# TS1.net
KiCad netlist of a schematic drawn in EAGLE
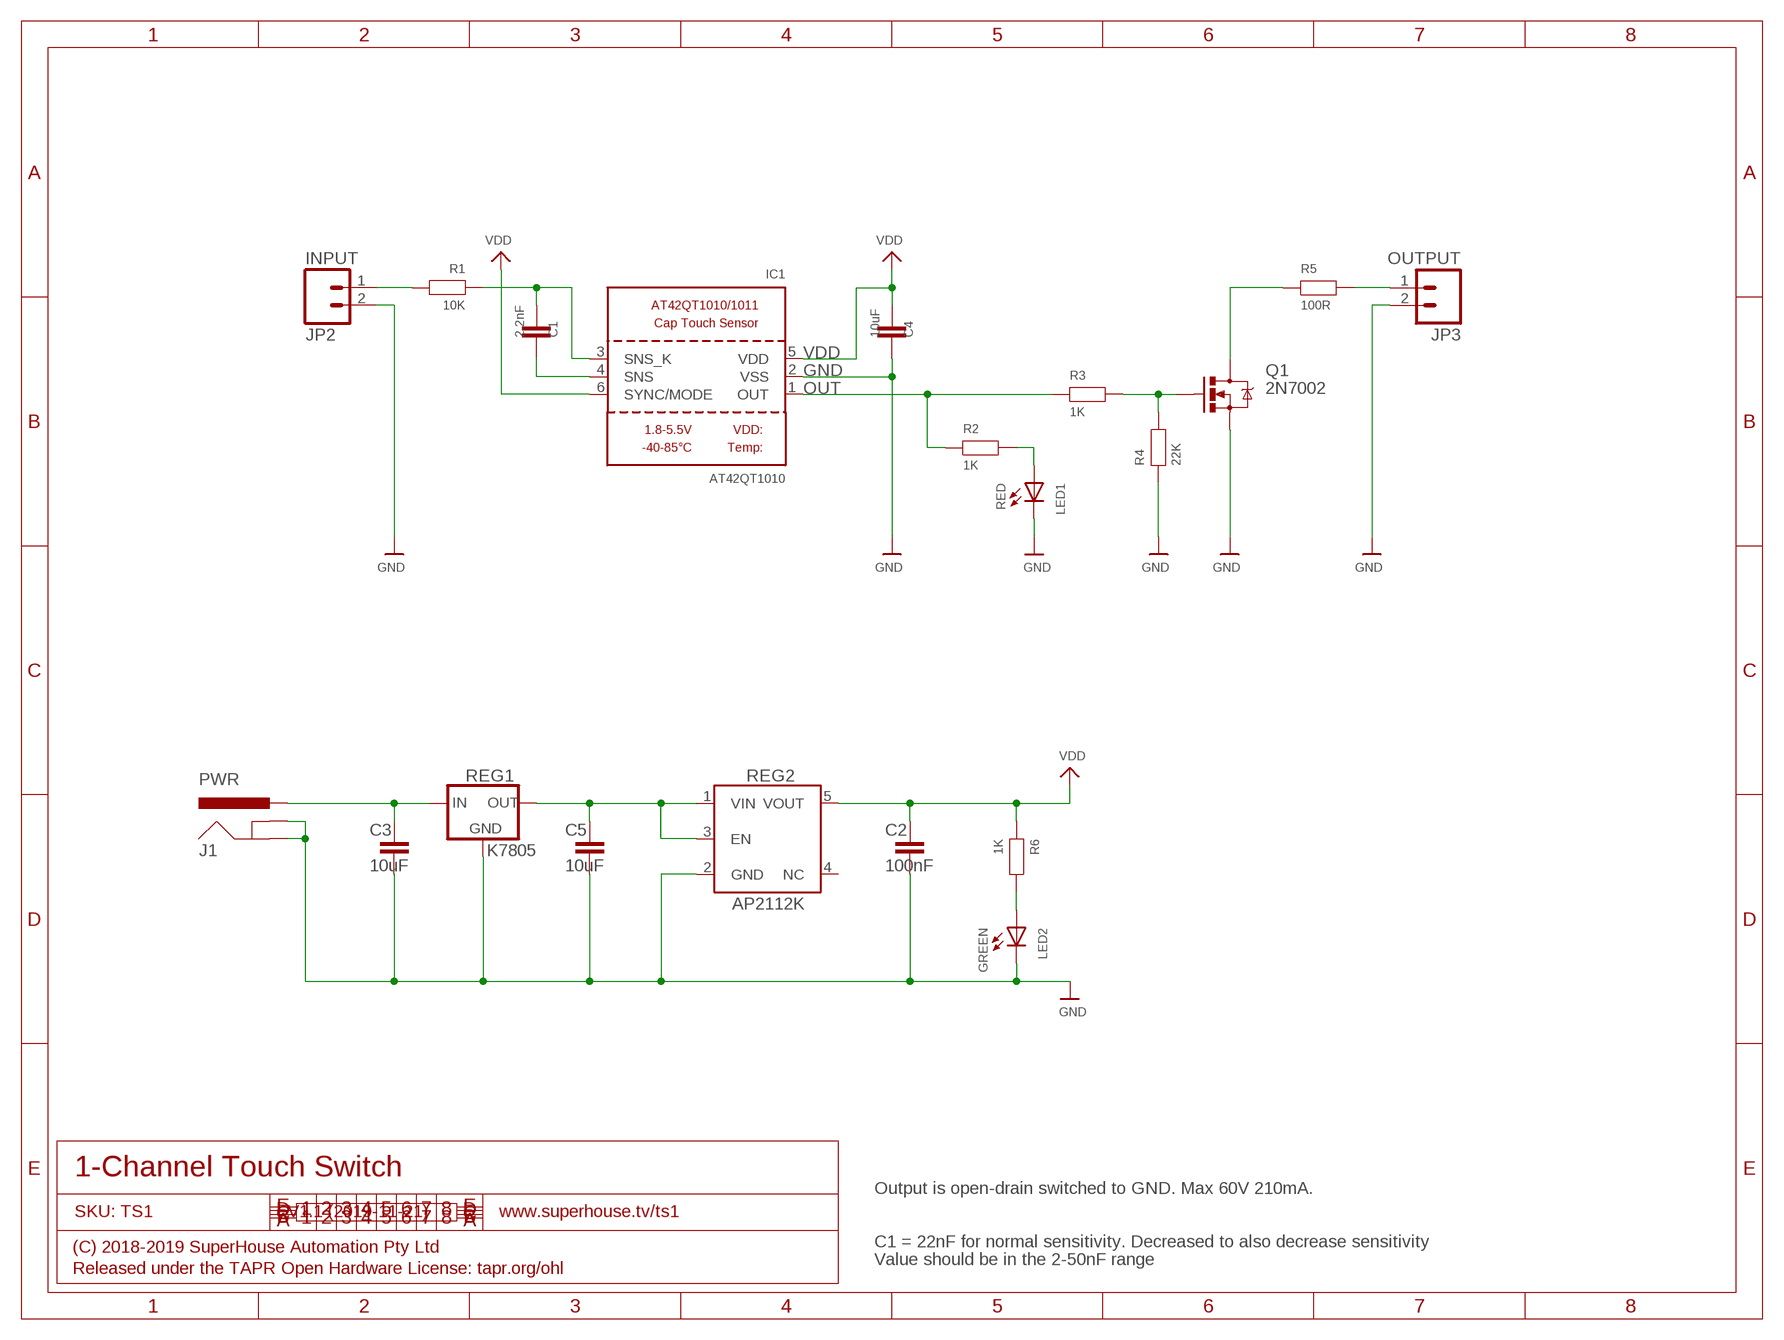
[diagram p0: schematic, sheet 1]

(export (version "E")
  (design (tool "Eeschema 10.0.6"))
  (components
    (comp (ref "C1")
      (value "2.2nF")
      (footprint "eagle-import:C0603")
      (libsource (lib "eagle-import") (part "CAP0603"))
    )
    (comp (ref "C2")
      (value "100nF")
      (footprint "eagle-import:C0603")
      (libsource (lib "eagle-import") (part "CAP0603"))
    )
    (comp (ref "C3")
      (value "10uF")
      (footprint "eagle-import:C0603")
      (libsource (lib "eagle-import") (part "CAP0603"))
    )
    (comp (ref "C4")
      (value "10uF")
      (footprint "eagle-import:C0603")
      (libsource (lib "eagle-import") (part "CAP0603"))
    )
    (comp (ref "C5")
      (value "10uF")
      (footprint "eagle-import:C0603")
      (libsource (lib "eagle-import") (part "CAP0603"))
    )
    (comp (ref "IC1")
      (value "AT42QT1010")
      (footprint "eagle-import:SOT23-6")
      (libsource (lib "eagle-import") (part "AT42QT1010/1"))
    )
    (comp (ref "J1")
      (value "PWR")
      (footprint "eagle-import:POWER_JACK_SLOTS")
      (libsource (lib "eagle-import") (part "POWER_JACK-SLOTS"))
    )
    (comp (ref "JP2")
      (value "INPUT")
      (footprint "eagle-import:1X02-S")
      (libsource (lib "eagle-import") (part "M02-SOCKET"))
    )
    (comp (ref "JP3")
      (value "OUTPUT")
      (footprint "eagle-import:1X02-S")
      (libsource (lib "eagle-import") (part "M02-SOCKET"))
    )
    (comp (ref "LED1")
      (value "RED")
      (footprint "eagle-import:LED-0603")
      (libsource (lib "eagle-import") (part "LED0603"))
    )
    (comp (ref "LED2")
      (value "GREEN")
      (footprint "eagle-import:LED-0603")
      (libsource (lib "eagle-import") (part "LED0603"))
    )
    (comp (ref "Q1")
      (value "2N7002")
      (footprint "eagle-import:SOT23-3")
      (libsource (lib "eagle-import") (part "MOSFET-NCHANNEL-233"))
    )
    (comp (ref "R1")
      (value "10K")
      (footprint "eagle-import:R0603")
      (libsource (lib "eagle-import") (part "RESISTOR0603"))
    )
    (comp (ref "R2")
      (value "1K")
      (footprint "eagle-import:R0603")
      (libsource (lib "eagle-import") (part "RESISTOR0603"))
    )
    (comp (ref "R3")
      (value "1K")
      (footprint "eagle-import:R0603")
      (libsource (lib "eagle-import") (part "RESISTOR0603"))
    )
    (comp (ref "R4")
      (value "22K")
      (footprint "eagle-import:R0603")
      (libsource (lib "eagle-import") (part "RESISTOR0603"))
    )
    (comp (ref "R5")
      (value "100R")
      (footprint "eagle-import:R0603")
      (libsource (lib "eagle-import") (part "RESISTOR0603"))
    )
    (comp (ref "R6")
      (value "1K")
      (footprint "eagle-import:R0603")
      (libsource (lib "eagle-import") (part "RESISTOR0603"))
    )
    (comp (ref "REG1")
      (value "K7805")
      (footprint "eagle-import:K78XX-500R3")
      (libsource (lib "eagle-import") (part "K78XX-500R3"))
    )
    (comp (ref "REG2")
      (value "AP2112KSOT25")
      (footprint "eagle-import:SOT23-5")
      (libsource (lib "eagle-import") (part "AP2112KSOT25"))
    )
  )
  (nets
    (net (code "1") (name "/OUT") (class "Default")
      (node (ref "IC1") (pin "1") (pinfunction "OUT_1") (pintype "output"))
      (node (ref "R2") (pin "1") (pinfunction "1_1") (pintype "passive"))
      (node (ref "R3") (pin "1") (pinfunction "1_1") (pintype "passive"))
    )
    (net (code "2") (name "GND") (class "Default")
      (node (ref "C2") (pin "2") (pinfunction "2_2") (pintype "passive"))
      (node (ref "C3") (pin "2") (pinfunction "2_2") (pintype "passive"))
      (node (ref "C4") (pin "2") (pinfunction "2_2") (pintype "passive"))
      (node (ref "C5") (pin "2") (pinfunction "2_2") (pintype "passive"))
      (node (ref "IC1") (pin "2") (pinfunction "VSS_2") (pintype "power_in"))
      (node (ref "J1") (pin "GND") (pinfunction "GND_GND") (pintype "bidirectional"))
      (node (ref "J1") (pin "GNDBREAK") (pinfunction "GNDBREAK_GNDBREAK") (pintype "bidirectional"))
      (node (ref "JP2") (pin "2") (pinfunction "2_2") (pintype "passive"))
      (node (ref "JP3") (pin "2") (pinfunction "2_2") (pintype "passive"))
      (node (ref "LED1") (pin "C") (pinfunction "C_C") (pintype "passive"))
      (node (ref "LED2") (pin "C") (pinfunction "C_C") (pintype "passive"))
      (node (ref "Q1") (pin "2") (pinfunction "S_2") (pintype "passive"))
      (node (ref "R4") (pin "1") (pinfunction "1_1") (pintype "passive"))
      (node (ref "REG1") (pin "2") (pinfunction "GND_2") (pintype "input"))
      (node (ref "REG2") (pin "2") (pinfunction "GND_2") (pintype "bidirectional"))
    )
    (net (code "3") (name "Net-(IC1-SNS)") (class "Default")
      (node (ref "C1") (pin "2") (pinfunction "2_2") (pintype "passive"))
      (node (ref "IC1") (pin "4") (pinfunction "SNS_4") (pintype "bidirectional"))
    )
    (net (code "4") (name "Net-(IC1-SNS_K)") (class "Default")
      (node (ref "C1") (pin "1") (pinfunction "1_1") (pintype "passive"))
      (node (ref "IC1") (pin "3") (pinfunction "SNS_K_3") (pintype "bidirectional"))
      (node (ref "R1") (pin "1") (pinfunction "1_1") (pintype "passive"))
    )
    (net (code "5") (name "Net-(JP2-Pad1)") (class "Default")
      (node (ref "JP2") (pin "1") (pinfunction "1_1") (pintype "passive"))
      (node (ref "R1") (pin "2") (pinfunction "2_2") (pintype "passive"))
    )
    (net (code "6") (name "Net-(JP3-Pad1)") (class "Default")
      (node (ref "JP3") (pin "1") (pinfunction "1_1") (pintype "passive"))
      (node (ref "R5") (pin "2") (pinfunction "2_2") (pintype "passive"))
    )
    (net (code "7") (name "Net-(LED1-PadA)") (class "Default")
      (node (ref "LED1") (pin "A") (pinfunction "A_A") (pintype "passive"))
      (node (ref "R2") (pin "2") (pinfunction "2_2") (pintype "passive"))
    )
    (net (code "8") (name "Net-(LED2-PadA)") (class "Default")
      (node (ref "LED2") (pin "A") (pinfunction "A_A") (pintype "passive"))
      (node (ref "R6") (pin "2") (pinfunction "2_2") (pintype "passive"))
    )
    (net (code "9") (name "Net-(Q1-D)") (class "Default")
      (node (ref "Q1") (pin "3") (pinfunction "D_3") (pintype "passive"))
      (node (ref "R5") (pin "1") (pinfunction "1_1") (pintype "passive"))
    )
    (net (code "10") (name "Net-(Q1-G)") (class "Default")
      (node (ref "Q1") (pin "1") (pinfunction "G_1") (pintype "passive"))
      (node (ref "R3") (pin "2") (pinfunction "2_2") (pintype "passive"))
      (node (ref "R4") (pin "2") (pinfunction "2_2") (pintype "passive"))
    )
    (net (code "11") (name "Net-(REG1-IN)") (class "Default")
      (node (ref "C3") (pin "1") (pinfunction "1_1") (pintype "passive"))
      (node (ref "J1") (pin "PWR") (pinfunction "PWR_PWR") (pintype "bidirectional"))
      (node (ref "REG1") (pin "1") (pinfunction "IN_1") (pintype "input"))
    )
    (net (code "12") (name "Net-(REG1-OUT)") (class "Default")
      (node (ref "C5") (pin "1") (pinfunction "1_1") (pintype "passive"))
      (node (ref "REG1") (pin "3") (pinfunction "OUT_3") (pintype "output"))
      (node (ref "REG2") (pin "1") (pinfunction "VIN_1") (pintype "bidirectional"))
      (node (ref "REG2") (pin "3") (pinfunction "EN_3") (pintype "bidirectional"))
    )
    (net (code "13") (name "VDD") (class "Default")
      (node (ref "C2") (pin "1") (pinfunction "1_1") (pintype "passive"))
      (node (ref "C4") (pin "1") (pinfunction "1_1") (pintype "passive"))
      (node (ref "IC1") (pin "5") (pinfunction "VDD_5") (pintype "power_in"))
      (node (ref "IC1") (pin "6") (pinfunction "SYNC/MODE_6") (pintype "input"))
      (node (ref "R6") (pin "1") (pinfunction "1_1") (pintype "passive"))
      (node (ref "REG2") (pin "5") (pinfunction "VOUT_5") (pintype "bidirectional"))
    )
    (net (code "14") (name "unconnected-(REG2-NC-Pad4)") (class "Default")
      (node (ref "REG2") (pin "4") (pinfunction "NC_4") (pintype "bidirectional"))
    )
  )
)
